# DC_DC_Converter_Eagle.net
KiCad netlist of a schematic drawn in EAGLE
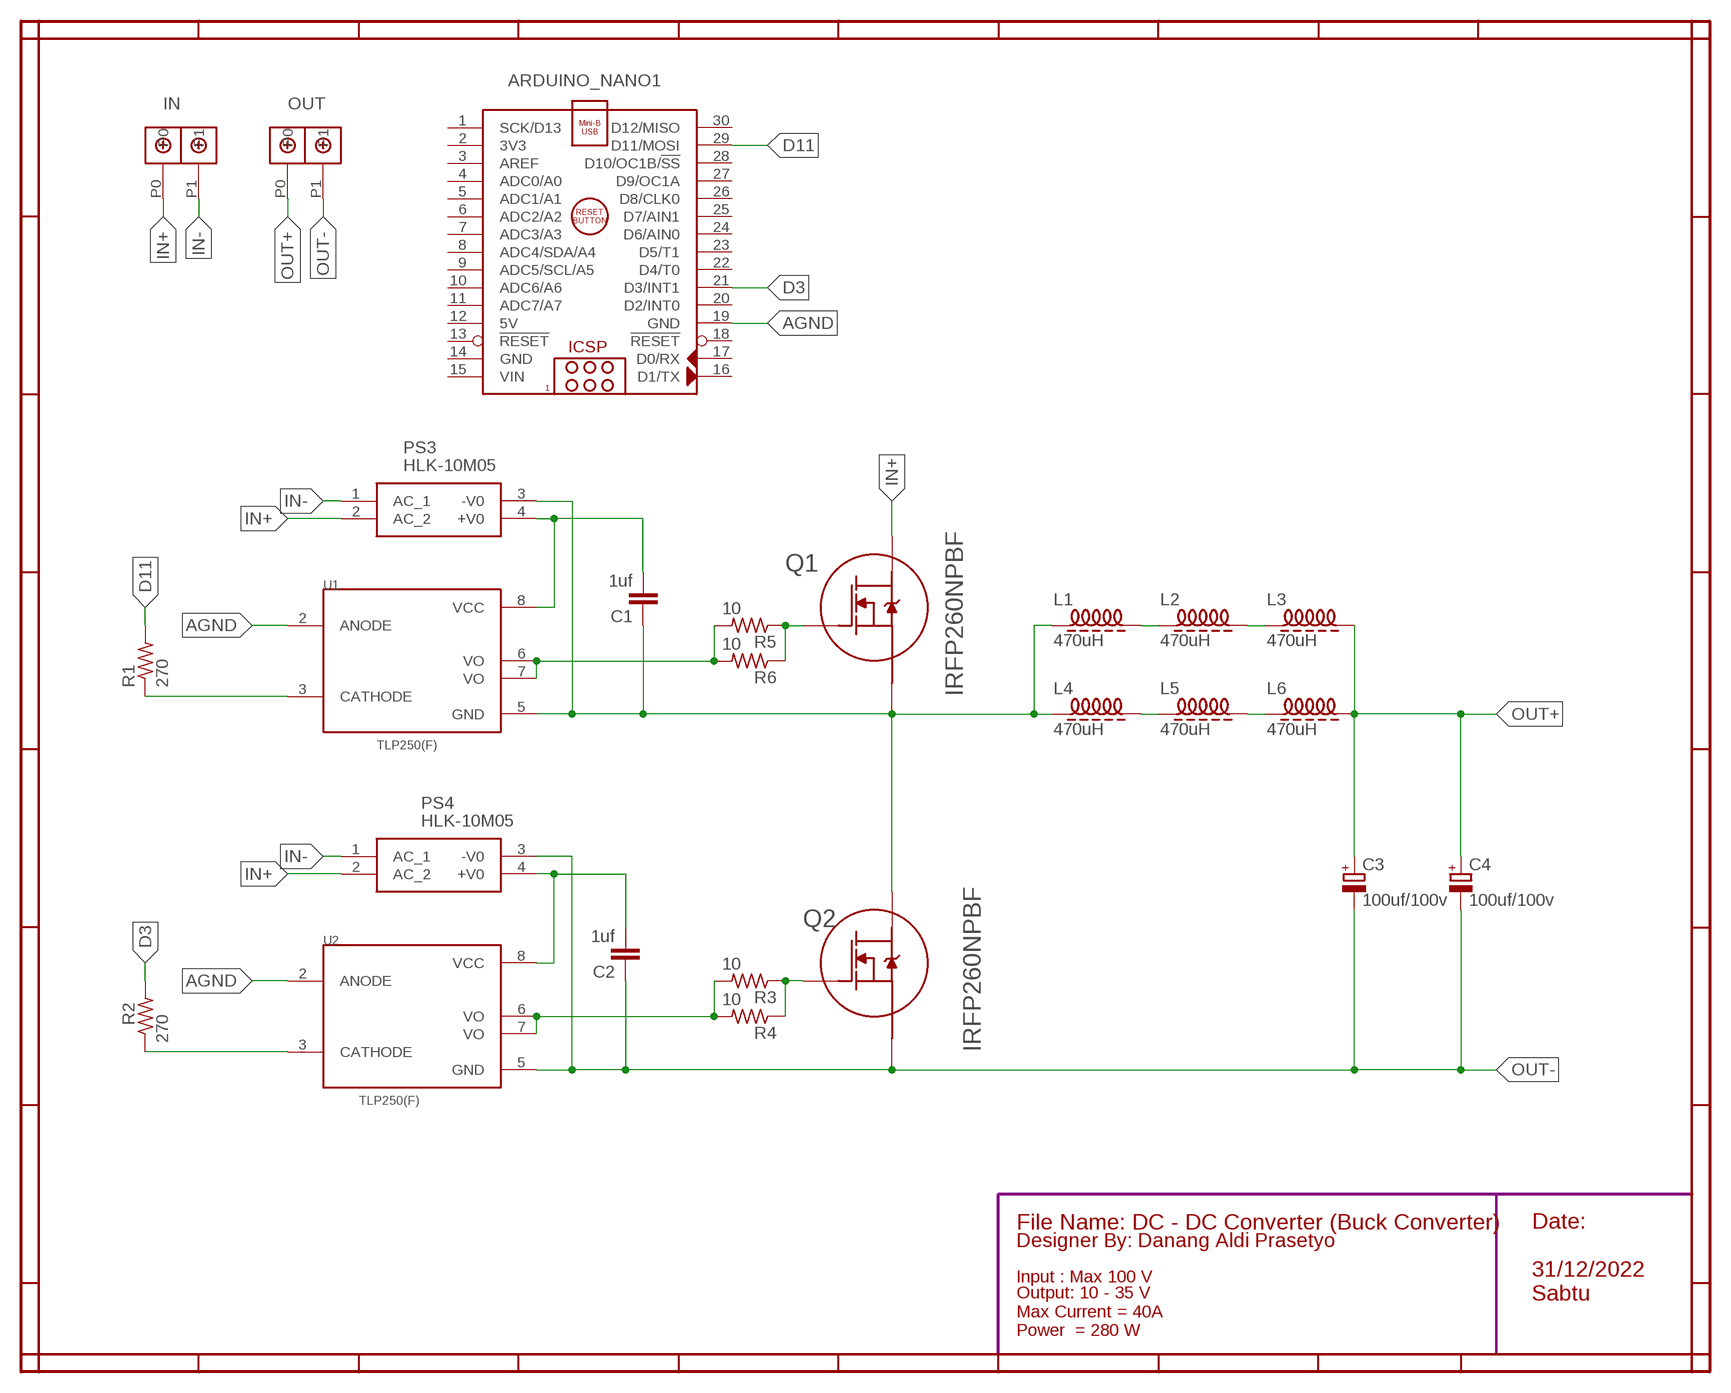
[diagram p0: schematic, sheet 1]

(export (version "E")
  (design (tool "Eeschema 10.0.6"))
  (components
    (comp (ref "ARDUINO_NANO1")
      (value "ARDUINO_NANO")
      (footprint "eagle-import:ARDUINO_NANO")
      (libsource (lib "eagle-import") (part "ARDUINO_NANO"))
    )
    (comp (ref "C1")
      (value "1uf")
      (footprint "eagle-import:C025-024X044")
      (libsource (lib "eagle-import") (part "C-EU025-024X044"))
    )
    (comp (ref "C2")
      (value "1uf")
      (footprint "eagle-import:C025-024X044")
      (libsource (lib "eagle-import") (part "C-EU025-024X044"))
    )
    (comp (ref "C3")
      (value "100uf/100v")
      (footprint "eagle-import:E5-10,5")
      (libsource (lib "eagle-import") (part "CPOL-EUE5-10.5"))
    )
    (comp (ref "C4")
      (value "100uf/100v")
      (footprint "eagle-import:E5-10,5")
      (libsource (lib "eagle-import") (part "CPOL-EUE5-10.5"))
    )
    (comp (ref "L1")
      (value "470uH")
      (footprint "eagle-import:Z15_15")
      (libsource (lib "eagle-import") (part "Z?CCW15/15"))
    )
    (comp (ref "L2")
      (value "470uH")
      (footprint "eagle-import:Z15_15")
      (libsource (lib "eagle-import") (part "Z?CCW15/15"))
    )
    (comp (ref "L3")
      (value "470uH")
      (footprint "eagle-import:Z15_15")
      (libsource (lib "eagle-import") (part "Z?CCW15/15"))
    )
    (comp (ref "L4")
      (value "470uH")
      (footprint "eagle-import:Z15_15")
      (libsource (lib "eagle-import") (part "Z?CCW15/15"))
    )
    (comp (ref "L5")
      (value "470uH")
      (footprint "eagle-import:Z15_15")
      (libsource (lib "eagle-import") (part "Z?CCW15/15"))
    )
    (comp (ref "L6")
      (value "470uH")
      (footprint "eagle-import:Z15_15")
      (libsource (lib "eagle-import") (part "Z?CCW15/15"))
    )
    (comp (ref "PS3")
      (value "HLK-10M05")
      (footprint "eagle-import:HLK10M05")
      (fields (field (name "MF") "Hi-link"))
      (libsource (lib "eagle-import") (part "HLK-10M05"))
    )
    (comp (ref "PS4")
      (value "HLK-10M05")
      (footprint "eagle-import:HLK10M05")
      (fields (field (name "MF") "Hi-link"))
      (libsource (lib "eagle-import") (part "HLK-10M05"))
    )
    (comp (ref "Q1")
      (value "IRFP260NPBF")
      (footprint "eagle-import:TO545P1590X530X2460-3")
      (fields (field (name "MF") "Infineon Technologies"))
      (libsource (lib "eagle-import") (part "IRFP260NPBF"))
    )
    (comp (ref "Q2")
      (value "IRFP260NPBF")
      (footprint "eagle-import:TO545P1590X530X2460-3")
      (fields (field (name "MF") "Infineon Technologies"))
      (libsource (lib "eagle-import") (part "IRFP260NPBF"))
    )
    (comp (ref "R1")
      (value "270")
      (footprint "eagle-import:0207_7")
      (libsource (lib "eagle-import") (part "R-US_0207/7"))
    )
    (comp (ref "R2")
      (value "270")
      (footprint "eagle-import:0207_7")
      (libsource (lib "eagle-import") (part "R-US_0207/7"))
    )
    (comp (ref "R3")
      (value "10")
      (footprint "eagle-import:0207_7")
      (libsource (lib "eagle-import") (part "R-US_0207/7"))
    )
    (comp (ref "R4")
      (value "10")
      (footprint "eagle-import:0207_7")
      (libsource (lib "eagle-import") (part "R-US_0207/7"))
    )
    (comp (ref "R5")
      (value "10")
      (footprint "eagle-import:0207_7")
      (libsource (lib "eagle-import") (part "R-US_0207/7"))
    )
    (comp (ref "R6")
      (value "10")
      (footprint "eagle-import:0207_7")
      (libsource (lib "eagle-import") (part "R-US_0207/7"))
    )
    (comp (ref "U$1")
      (value "DBCONN-1X2")
      (footprint "eagle-import:DBCONN-1X2")
      (libsource (lib "eagle-import") (part "DBCONN-1X2"))
    )
    (comp (ref "U$2")
      (value "DBCONN-1X2")
      (footprint "eagle-import:DBCONN-1X2")
      (libsource (lib "eagle-import") (part "DBCONN-1X2"))
    )
    (comp (ref "U1")
      (value "TLP250(F)")
      (footprint "eagle-import:DIP1016W50P254L966H380Q8P")
      (fields (field (name "MF") "Toshiba"))
      (libsource (lib "eagle-import") (part "TLP250(F)"))
    )
    (comp (ref "U2")
      (value "TLP250(F)")
      (footprint "eagle-import:DIP1016W50P254L966H380Q8P")
      (fields (field (name "MF") "Toshiba"))
      (libsource (lib "eagle-import") (part "TLP250(F)"))
    )
  )
  (nets
    (net (code "1") (name "/5V") (class "Default")
      (node (ref "ARDUINO_NANO1") (pin "12") (pinfunction "5V_12") (pintype "power_in"))
    )
    (net (code "2") (name "/GND") (class "Default")
      (node (ref "ARDUINO_NANO1") (pin "14") (pinfunction "GND_14") (pintype "power_in"))
    )
    (net (code "3") (name "/VIN") (class "Default")
      (node (ref "ARDUINO_NANO1") (pin "15") (pinfunction "VIN_15") (pintype "power_in"))
    )
    (net (code "4") (name "AGND") (class "Default")
      (node (ref "ARDUINO_NANO1") (pin "19") (pinfunction "GND_19") (pintype "power_in"))
      (node (ref "U1") (pin "2") (pinfunction "ANODE_2") (pintype "passive"))
      (node (ref "U2") (pin "2") (pinfunction "ANODE_2") (pintype "passive"))
    )
    (net (code "5") (name "D3") (class "Default")
      (node (ref "ARDUINO_NANO1") (pin "21") (pinfunction "D3/INT1_21") (pintype "bidirectional"))
      (node (ref "R2") (pin "2") (pinfunction "2_2") (pintype "passive"))
    )
    (net (code "6") (name "D11") (class "Default")
      (node (ref "ARDUINO_NANO1") (pin "29") (pinfunction "D11/MOSI_29") (pintype "bidirectional"))
      (node (ref "R1") (pin "2") (pinfunction "2_2") (pintype "passive"))
    )
    (net (code "7") (name "IN+") (class "Default")
      (node (ref "PS3") (pin "2") (pinfunction "AC_2_2") (pintype "bidirectional"))
      (node (ref "PS4") (pin "2") (pinfunction "AC_2_2") (pintype "bidirectional"))
      (node (ref "Q1") (pin "2") (pinfunction "D_2") (pintype "passive"))
      (node (ref "U$1") (pin "P0") (pinfunction "P0_P0") (pintype "bidirectional"))
    )
    (net (code "8") (name "IN-") (class "Default")
      (node (ref "PS3") (pin "1") (pinfunction "AC_1_1") (pintype "bidirectional"))
      (node (ref "PS4") (pin "1") (pinfunction "AC_1_1") (pintype "bidirectional"))
      (node (ref "U$1") (pin "P1") (pinfunction "P1_P1") (pintype "bidirectional"))
    )
    (net (code "9") (name "Net-(L1-Pad2)") (class "Default")
      (node (ref "L1") (pin "2") (pinfunction "2_2") (pintype "passive"))
      (node (ref "L2") (pin "1") (pinfunction "1_1") (pintype "passive"))
    )
    (net (code "10") (name "Net-(L2-Pad2)") (class "Default")
      (node (ref "L2") (pin "2") (pinfunction "2_2") (pintype "passive"))
      (node (ref "L3") (pin "1") (pinfunction "1_1") (pintype "passive"))
    )
    (net (code "11") (name "Net-(L4-Pad2)") (class "Default")
      (node (ref "L4") (pin "2") (pinfunction "2_2") (pintype "passive"))
      (node (ref "L5") (pin "1") (pinfunction "1_1") (pintype "passive"))
    )
    (net (code "12") (name "Net-(L5-Pad2)") (class "Default")
      (node (ref "L5") (pin "2") (pinfunction "2_2") (pintype "passive"))
      (node (ref "L6") (pin "1") (pinfunction "1_1") (pintype "passive"))
    )
    (net (code "13") (name "Net-(PS3-+V0)") (class "Default")
      (node (ref "C1") (pin "2") (pinfunction "2_2") (pintype "passive"))
      (node (ref "PS3") (pin "4") (pinfunction "+V0_4") (pintype "bidirectional"))
      (node (ref "U1") (pin "8") (pinfunction "VCC_8") (pintype "power_in"))
    )
    (net (code "14") (name "Net-(PS3--V0)") (class "Default")
      (node (ref "C1") (pin "1") (pinfunction "1_1") (pintype "passive"))
      (node (ref "L1") (pin "1") (pinfunction "1_1") (pintype "passive"))
      (node (ref "L4") (pin "1") (pinfunction "1_1") (pintype "passive"))
      (node (ref "PS3") (pin "3") (pinfunction "-V0_3") (pintype "bidirectional"))
      (node (ref "Q1") (pin "3") (pinfunction "S_3") (pintype "passive"))
      (node (ref "Q2") (pin "2") (pinfunction "D_2") (pintype "passive"))
      (node (ref "U1") (pin "5") (pinfunction "GND_5") (pintype "power_in"))
    )
    (net (code "15") (name "Net-(PS4-+V0)") (class "Default")
      (node (ref "C2") (pin "2") (pinfunction "2_2") (pintype "passive"))
      (node (ref "PS4") (pin "4") (pinfunction "+V0_4") (pintype "bidirectional"))
      (node (ref "U2") (pin "8") (pinfunction "VCC_8") (pintype "power_in"))
    )
    (net (code "16") (name "Net-(Q1-G)") (class "Default")
      (node (ref "Q1") (pin "1") (pinfunction "G_1") (pintype "passive"))
      (node (ref "R5") (pin "1") (pinfunction "1_1") (pintype "passive"))
      (node (ref "R6") (pin "1") (pinfunction "1_1") (pintype "passive"))
    )
    (net (code "17") (name "Net-(Q2-G)") (class "Default")
      (node (ref "Q2") (pin "1") (pinfunction "G_1") (pintype "passive"))
      (node (ref "R3") (pin "1") (pinfunction "1_1") (pintype "passive"))
      (node (ref "R4") (pin "1") (pinfunction "1_1") (pintype "passive"))
    )
    (net (code "18") (name "Net-(R3-Pad2)") (class "Default")
      (node (ref "R3") (pin "2") (pinfunction "2_2") (pintype "passive"))
      (node (ref "R4") (pin "2") (pinfunction "2_2") (pintype "passive"))
      (node (ref "U2") (pin "6") (pinfunction "VO_6") (pintype "output"))
      (node (ref "U2") (pin "7") (pinfunction "VO_7") (pintype "output"))
    )
    (net (code "19") (name "Net-(R5-Pad2)") (class "Default")
      (node (ref "R5") (pin "2") (pinfunction "2_2") (pintype "passive"))
      (node (ref "R6") (pin "2") (pinfunction "2_2") (pintype "passive"))
      (node (ref "U1") (pin "6") (pinfunction "VO_6") (pintype "output"))
      (node (ref "U1") (pin "7") (pinfunction "VO_7") (pintype "output"))
    )
    (net (code "20") (name "Net-(U1-CATHODE)") (class "Default")
      (node (ref "R1") (pin "1") (pinfunction "1_1") (pintype "passive"))
      (node (ref "U1") (pin "3") (pinfunction "CATHODE_3") (pintype "passive"))
    )
    (net (code "21") (name "Net-(U2-CATHODE)") (class "Default")
      (node (ref "R2") (pin "1") (pinfunction "1_1") (pintype "passive"))
      (node (ref "U2") (pin "3") (pinfunction "CATHODE_3") (pintype "passive"))
    )
    (net (code "22") (name "OUT+") (class "Default")
      (node (ref "C3") (pin "+") (pinfunction "+_+") (pintype "passive"))
      (node (ref "C4") (pin "+") (pinfunction "+_+") (pintype "passive"))
      (node (ref "L3") (pin "2") (pinfunction "2_2") (pintype "passive"))
      (node (ref "L6") (pin "2") (pinfunction "2_2") (pintype "passive"))
      (node (ref "U$2") (pin "P0") (pinfunction "P0_P0") (pintype "bidirectional"))
    )
    (net (code "23") (name "OUT-") (class "Default")
      (node (ref "C2") (pin "1") (pinfunction "1_1") (pintype "passive"))
      (node (ref "C3") (pin "-") (pinfunction "-_-") (pintype "passive"))
      (node (ref "C4") (pin "-") (pinfunction "-_-") (pintype "passive"))
      (node (ref "PS4") (pin "3") (pinfunction "-V0_3") (pintype "bidirectional"))
      (node (ref "Q2") (pin "3") (pinfunction "S_3") (pintype "passive"))
      (node (ref "U$2") (pin "P1") (pinfunction "P1_P1") (pintype "bidirectional"))
      (node (ref "U2") (pin "5") (pinfunction "GND_5") (pintype "power_in"))
    )
    (net (code "24") (name "unconnected-(ARDUINO_NANO1-3V3-Pad2)") (class "Default")
      (node (ref "ARDUINO_NANO1") (pin "2") (pinfunction "3V3_2") (pintype "output"))
    )
    (net (code "25") (name "unconnected-(ARDUINO_NANO1-ADC0{slash}A0-Pad4)") (class "Default")
      (node (ref "ARDUINO_NANO1") (pin "4") (pinfunction "ADC0/A0_4") (pintype "bidirectional"))
    )
    (net (code "26") (name "unconnected-(ARDUINO_NANO1-ADC1{slash}A1-Pad5)") (class "Default")
      (node (ref "ARDUINO_NANO1") (pin "5") (pinfunction "ADC1/A1_5") (pintype "bidirectional"))
    )
    (net (code "27") (name "unconnected-(ARDUINO_NANO1-ADC2{slash}A2-Pad6)") (class "Default")
      (node (ref "ARDUINO_NANO1") (pin "6") (pinfunction "ADC2/A2_6") (pintype "bidirectional"))
    )
    (net (code "28") (name "unconnected-(ARDUINO_NANO1-ADC3{slash}A3-Pad7)") (class "Default")
      (node (ref "ARDUINO_NANO1") (pin "7") (pinfunction "ADC3/A3_7") (pintype "bidirectional"))
    )
    (net (code "29") (name "unconnected-(ARDUINO_NANO1-ADC4{slash}SDA{slash}A4-Pad8)") (class "Default")
      (node (ref "ARDUINO_NANO1") (pin "8") (pinfunction "ADC4/SDA/A4_8") (pintype "bidirectional"))
    )
    (net (code "30") (name "unconnected-(ARDUINO_NANO1-ADC5{slash}SCL{slash}A5-Pad9)") (class "Default")
      (node (ref "ARDUINO_NANO1") (pin "9") (pinfunction "ADC5/SCL/A5_9") (pintype "bidirectional"))
    )
    (net (code "31") (name "unconnected-(ARDUINO_NANO1-ADC6{slash}A6-Pad10)") (class "Default")
      (node (ref "ARDUINO_NANO1") (pin "10") (pinfunction "ADC6/A6_10") (pintype "bidirectional"))
    )
    (net (code "32") (name "unconnected-(ARDUINO_NANO1-ADC7{slash}A7-Pad11)") (class "Default")
      (node (ref "ARDUINO_NANO1") (pin "11") (pinfunction "ADC7/A7_11") (pintype "bidirectional"))
    )
    (net (code "33") (name "unconnected-(ARDUINO_NANO1-AREF-Pad3)") (class "Default")
      (node (ref "ARDUINO_NANO1") (pin "3") (pinfunction "AREF_3") (pintype "input"))
    )
    (net (code "34") (name "unconnected-(ARDUINO_NANO1-D0{slash}RX-Pad17)") (class "Default")
      (node (ref "ARDUINO_NANO1") (pin "17") (pinfunction "D0/RX_17") (pintype "bidirectional"))
    )
    (net (code "35") (name "unconnected-(ARDUINO_NANO1-D1{slash}TX-Pad16)") (class "Default")
      (node (ref "ARDUINO_NANO1") (pin "16") (pinfunction "D1/TX_16") (pintype "bidirectional"))
    )
    (net (code "36") (name "unconnected-(ARDUINO_NANO1-D2{slash}INT0-Pad20)") (class "Default")
      (node (ref "ARDUINO_NANO1") (pin "20") (pinfunction "D2/INT0_20") (pintype "bidirectional"))
    )
    (net (code "37") (name "unconnected-(ARDUINO_NANO1-D4{slash}T0-Pad22)") (class "Default")
      (node (ref "ARDUINO_NANO1") (pin "22") (pinfunction "D4/T0_22") (pintype "bidirectional"))
    )
    (net (code "38") (name "unconnected-(ARDUINO_NANO1-D5{slash}T1-Pad23)") (class "Default")
      (node (ref "ARDUINO_NANO1") (pin "23") (pinfunction "D5/T1_23") (pintype "bidirectional"))
    )
    (net (code "39") (name "unconnected-(ARDUINO_NANO1-D6{slash}AIN0-Pad24)") (class "Default")
      (node (ref "ARDUINO_NANO1") (pin "24") (pinfunction "D6/AIN0_24") (pintype "bidirectional"))
    )
    (net (code "40") (name "unconnected-(ARDUINO_NANO1-D7{slash}AIN1-Pad25)") (class "Default")
      (node (ref "ARDUINO_NANO1") (pin "25") (pinfunction "D7/AIN1_25") (pintype "bidirectional"))
    )
    (net (code "41") (name "unconnected-(ARDUINO_NANO1-D8{slash}CLK0-Pad26)") (class "Default")
      (node (ref "ARDUINO_NANO1") (pin "26") (pinfunction "D8/CLK0_26") (pintype "bidirectional"))
    )
    (net (code "42") (name "unconnected-(ARDUINO_NANO1-D9{slash}OC1A-Pad27)") (class "Default")
      (node (ref "ARDUINO_NANO1") (pin "27") (pinfunction "D9/OC1A_27") (pintype "bidirectional"))
    )
    (net (code "43") (name "unconnected-(ARDUINO_NANO1-D10{slash}OC1B{slash}~{SS}-Pad28)") (class "Default")
      (node (ref "ARDUINO_NANO1") (pin "28") (pinfunction "D10/OC1B/~{SS}_28") (pintype "bidirectional"))
    )
    (net (code "44") (name "unconnected-(ARDUINO_NANO1-D12{slash}MISO-Pad30)") (class "Default")
      (node (ref "ARDUINO_NANO1") (pin "30") (pinfunction "D12/MISO_30") (pintype "bidirectional"))
    )
    (net (code "45") (name "unconnected-(ARDUINO_NANO1-SCK{slash}D13-Pad1)") (class "Default")
      (node (ref "ARDUINO_NANO1") (pin "1") (pinfunction "SCK/D13_1") (pintype "bidirectional"))
    )
    (net (code "46") (name "unconnected-(ARDUINO_NANO1-~{RESET}-Pad13)") (class "Default")
      (node (ref "ARDUINO_NANO1") (pin "13") (pinfunction "~{RESET}_13") (pintype "input"))
    )
    (net (code "47") (name "unconnected-(ARDUINO_NANO1-~{RESET}-Pad18)") (class "Default")
      (node (ref "ARDUINO_NANO1") (pin "18") (pinfunction "~{RESET}_18") (pintype "input"))
    )
  )
)
